# Tetrahedron_Schematic_source.net
KiCad netlist of a schematic drawn in EAGLE
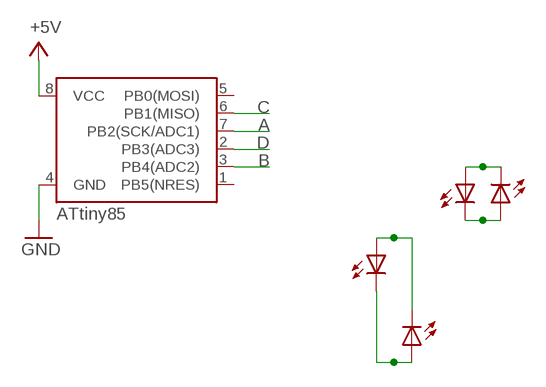
[diagram p0: schematic, sheet 1]

(export (version "E")
  (design (tool "Eeschema 10.0.6"))
  (components
    (comp (ref "LED1")
      (value "LED3MM")
      (footprint "eagle-import:LED3MM")
      (libsource (lib "eagle-import") (part "LED3MM"))
    )
    (comp (ref "LED2")
      (value "LED3MM")
      (footprint "eagle-import:LED3MM")
      (libsource (lib "eagle-import") (part "LED3MM"))
    )
    (comp (ref "LED3")
      (value "LED3MM")
      (footprint "eagle-import:LED3MM")
      (libsource (lib "eagle-import") (part "LED3MM"))
    )
    (comp (ref "LED4")
      (value "LED3MM")
      (footprint "eagle-import:LED3MM")
      (libsource (lib "eagle-import") (part "LED3MM"))
    )
    (comp (ref "U1")
      (value "ATtiny85")
      (footprint "eagle-import:DIP08")
      (libsource (lib "eagle-import") (part "ATTINY45TINY85-20-DIP"))
    )
  )
  (nets
    (net (code "1") (name "+5V") (class "Default")
      (node (ref "U1") (pin "8") (pinfunction "VCC_8") (pintype "bidirectional"))
    )
    (net (code "2") (name "/A") (class "Default")
      (node (ref "U1") (pin "7") (pinfunction "PB2(SCK/ADC1)_7") (pintype "bidirectional"))
    )
    (net (code "3") (name "/B") (class "Default")
      (node (ref "U1") (pin "3") (pinfunction "PB4(ADC2)_3") (pintype "bidirectional"))
    )
    (net (code "4") (name "/C") (class "Default")
      (node (ref "U1") (pin "6") (pinfunction "PB1(MISO)_6") (pintype "bidirectional"))
    )
    (net (code "5") (name "/D") (class "Default")
      (node (ref "U1") (pin "2") (pinfunction "PB3(ADC3)_2") (pintype "bidirectional"))
    )
    (net (code "6") (name "GND") (class "Default")
      (node (ref "U1") (pin "4") (pinfunction "GND_4") (pintype "bidirectional"))
    )
    (net (code "7") (name "Net-(LED1-C)") (class "Default")
      (node (ref "LED1") (pin "K") (pinfunction "C_K") (pintype "passive"))
      (node (ref "LED2") (pin "A") (pinfunction "A_A") (pintype "passive"))
    )
    (net (code "8") (name "Net-(LED2-C)") (class "Default")
      (node (ref "LED1") (pin "A") (pinfunction "A_A") (pintype "passive"))
      (node (ref "LED2") (pin "K") (pinfunction "C_K") (pintype "passive"))
    )
    (net (code "9") (name "Net-(LED3-C)") (class "Default")
      (node (ref "LED3") (pin "K") (pinfunction "C_K") (pintype "passive"))
      (node (ref "LED4") (pin "A") (pinfunction "A_A") (pintype "passive"))
    )
    (net (code "10") (name "Net-(LED4-C)") (class "Default")
      (node (ref "LED3") (pin "A") (pinfunction "A_A") (pintype "passive"))
      (node (ref "LED4") (pin "K") (pinfunction "C_K") (pintype "passive"))
    )
    (net (code "11") (name "unconnected-(U1-PB0(MOSI)-Pad5)") (class "Default")
      (node (ref "U1") (pin "5") (pinfunction "PB0(MOSI)_5") (pintype "bidirectional"))
    )
    (net (code "12") (name "unconnected-(U1-PB5(NRES)-Pad1)") (class "Default")
      (node (ref "U1") (pin "1") (pinfunction "PB5(NRES)_1") (pintype "bidirectional"))
    )
  )
)
